# 8-Bluetooth.net
KiCad netlist of a schematic drawn in Altium Designer
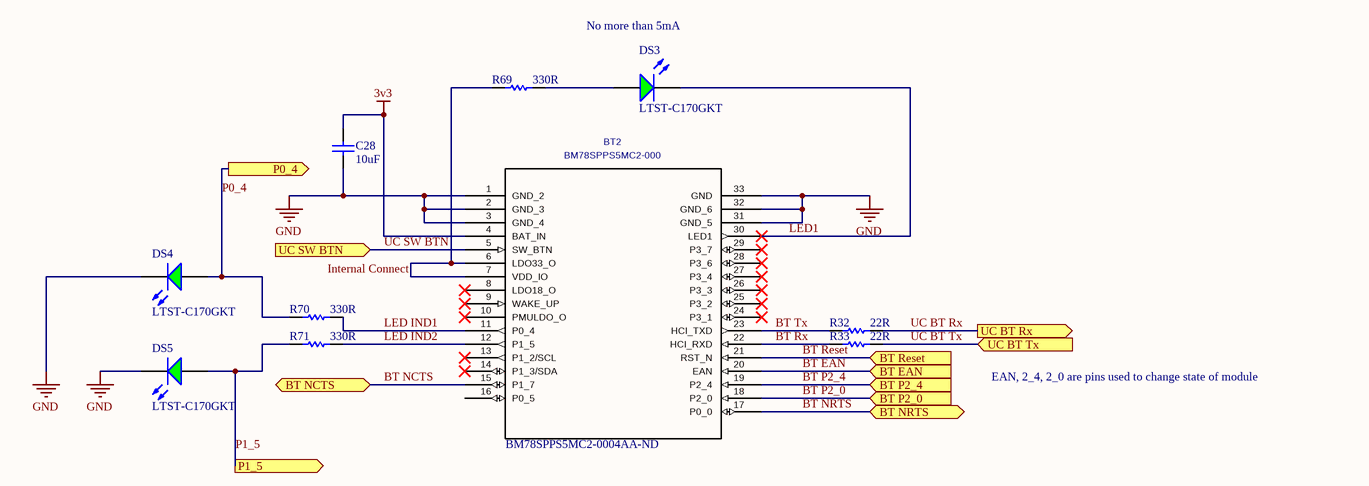
[diagram p0: 8-Bluetooth.SchDoc]

(export (version "E")
  (design (tool "Eeschema 10.0.6"))
  (components
    (comp (ref "BT2")
      (value "BM78SPPS5MC2-000")
      (footprint "BM78SPPS5MC2/NC2")
      (fields
        (field (name "MANUFACTURER_PART_NUMBER") "BM78SPPS5MC2-0006AA")
        (field (name "SUPPLIER PART NUMBER 1") "BM78SPPS5MC2-0004AA-ND")
        (field (name "COPYRIGHT") "Copyright (C) 2022 Ultra Librarian. All rights reserved.")
      )
      (libsource (lib "VCB20") (part "BM78SPPS5MC2-000"))
    )
    (comp (ref "C28")
      (value "10uF")
      (footprint "1608[0603]")
      (description "Capacitor")
      (fields
        (field (name "MANUFACTURER") "Yageo")
        (field (name "MANUFACTURER PART NUMBER") "CC0603KRX7R9BB104")
      )
      (libsource (lib "Miscellaneous Devices") (part "Cap"))
    )
    (comp (ref "DS3")
      (value "LTST-C170GKT")
      (footprint "LTST-C170GKT_V")
      (description "LED Uni-Color Green, 100 mW, 120 mA, -55 to 85 degC, 2-Pin SMD, RoHS, Tape and Reel")
      (fields (field (name "MANUFACTURER") "Lite-On"))
      (libsource (lib "Altium Content Vault") (part "LED-GREEN-AK-2"))
    )
    (comp (ref "DS4")
      (value "LTST-C170GKT")
      (footprint "LTST-C170GKT_V")
      (description "LED Uni-Color Green, 100 mW, 120 mA, -55 to 85 degC, 2-Pin SMD, RoHS, Tape and Reel")
      (fields (field (name "MANUFACTURER") "Lite-On"))
      (libsource (lib "Altium Content Vault") (part "LED-GREEN-AK-2"))
    )
    (comp (ref "DS5")
      (value "LTST-C170GKT")
      (footprint "LTST-C170GKT_V")
      (description "LED Uni-Color Green, 100 mW, 120 mA, -55 to 85 degC, 2-Pin SMD, RoHS, Tape and Reel")
      (fields (field (name "MANUFACTURER") "Lite-On"))
      (libsource (lib "Altium Content Vault") (part "LED-GREEN-AK-2"))
    )
    (comp (ref "R32")
      (value "22R")
      (footprint "1608[0603]")
      (description "Resistor")
      (fields
        (field (name "MANUFACTURER") "Yageo")
        (field (name "MANUFACTURER PART NUMBER") "RC0603JR-0722RL")
      )
      (libsource (lib "Miscellaneous Devices") (part "Res1"))
    )
    (comp (ref "R33")
      (value "22R")
      (footprint "1608[0603]")
      (description "Resistor")
      (fields
        (field (name "MANUFACTURER") "Yageo")
        (field (name "MANUFACTURER PART NUMBER") "RC0603JR-0722RL")
      )
      (libsource (lib "Miscellaneous Devices") (part "Res1"))
    )
    (comp (ref "R69")
      (value "330R")
      (footprint "1608[0603]")
      (description "Resistor")
      (fields
        (field (name "MANUFACTURER") "Yageo")
        (field (name "MANUFACTURER PART NUMBER") "RC0603JR-0722RL")
      )
      (libsource (lib "Miscellaneous Devices") (part "Res1"))
    )
    (comp (ref "R70")
      (value "330R")
      (footprint "1608[0603]")
      (description "Resistor")
      (fields
        (field (name "MANUFACTURER") "Yageo")
        (field (name "MANUFACTURER PART NUMBER") "RC0603JR-0722RL")
      )
      (libsource (lib "Miscellaneous Devices") (part "Res1"))
    )
    (comp (ref "R71")
      (value "330R")
      (footprint "1608[0603]")
      (description "Resistor")
      (fields
        (field (name "MANUFACTURER") "Yageo")
        (field (name "MANUFACTURER PART NUMBER") "RC0603JR-0722RL")
      )
      (libsource (lib "Miscellaneous Devices") (part "Res1"))
    )
  )
  (nets
    (net (code "1") (name "/BT EAN") (class "Default")
      (node (ref "BT2") (pin "20") (pinfunction "EAN_20") (pintype "input"))
    )
    (net (code "2") (name "/BT NCTS") (class "Default")
      (node (ref "BT2") (pin "15") (pinfunction "P1_7_15") (pintype "bidirectional"))
    )
    (net (code "3") (name "/BT NRTS") (class "Default")
      (node (ref "BT2") (pin "17") (pinfunction "P0_0_17") (pintype "bidirectional"))
    )
    (net (code "4") (name "/BT P2_0") (class "Default")
      (node (ref "BT2") (pin "18") (pinfunction "P2_0_18") (pintype "input"))
    )
    (net (code "5") (name "/BT P2_4") (class "Default")
      (node (ref "BT2") (pin "19") (pinfunction "P2_4_19") (pintype "input"))
    )
    (net (code "6") (name "/BT Reset") (class "Default")
      (node (ref "BT2") (pin "21") (pinfunction "RST_N_21") (pintype "input"))
    )
    (net (code "7") (name "/BT Rx") (class "Default")
      (node (ref "BT2") (pin "22") (pinfunction "HCI_RXD_22") (pintype "input"))
      (node (ref "R33") (pin "1") (pinfunction "1_1") (pintype "passive"))
    )
    (net (code "8") (name "/BT Tx") (class "Default")
      (node (ref "BT2") (pin "23") (pinfunction "HCI_TXD_23") (pintype "output"))
      (node (ref "R32") (pin "1") (pinfunction "1_1") (pintype "passive"))
    )
    (net (code "9") (name "/Internal Connect") (class "Default")
      (node (ref "BT2") (pin "6") (pinfunction "LDO33_O_6") (pintype "power_in"))
      (node (ref "BT2") (pin "7") (pinfunction "VDD_IO_7") (pintype "power_in"))
      (node (ref "R69") (pin "1") (pinfunction "1_1") (pintype "passive"))
    )
    (net (code "10") (name "/LED IND1") (class "Default")
      (node (ref "BT2") (pin "11") (pinfunction "P0_4_11") (pintype "output"))
      (node (ref "R70") (pin "2") (pinfunction "2_2") (pintype "passive"))
    )
    (net (code "11") (name "/LED IND2") (class "Default")
      (node (ref "BT2") (pin "12") (pinfunction "P1_5_12") (pintype "output"))
      (node (ref "R71") (pin "2") (pinfunction "2_2") (pintype "passive"))
    )
    (net (code "12") (name "/LED1") (class "Default")
      (node (ref "BT2") (pin "30") (pinfunction "LED1_30") (pintype "output"))
      (node (ref "DS3") (pin "2") (pinfunction "K_2") (pintype "passive"))
    )
    (net (code "13") (name "/P0_4") (class "Default")
      (node (ref "DS4") (pin "1") (pinfunction "A_1") (pintype "passive"))
      (node (ref "R70") (pin "1") (pinfunction "1_1") (pintype "passive"))
    )
    (net (code "14") (name "/P1_5") (class "Default")
      (node (ref "DS5") (pin "1") (pinfunction "A_1") (pintype "passive"))
      (node (ref "R71") (pin "1") (pinfunction "1_1") (pintype "passive"))
    )
    (net (code "15") (name "/UC BT Rx") (class "Default")
      (node (ref "R32") (pin "2") (pinfunction "2_2") (pintype "passive"))
    )
    (net (code "16") (name "/UC BT Tx") (class "Default")
      (node (ref "R33") (pin "2") (pinfunction "2_2") (pintype "passive"))
    )
    (net (code "17") (name "/UC SW BTN") (class "Default")
      (node (ref "BT2") (pin "5") (pinfunction "SW_BTN_5") (pintype "input"))
    )
    (net (code "18") (name "3v3") (class "Default")
      (node (ref "BT2") (pin "4") (pinfunction "BAT_IN_4") (pintype "power_in"))
      (node (ref "C28") (pin "2") (pinfunction "2_2") (pintype "passive"))
    )
    (net (code "19") (name "GND") (class "Default")
      (node (ref "BT2") (pin "1") (pinfunction "GND_2_1") (pintype "power_in"))
      (node (ref "BT2") (pin "2") (pinfunction "GND_3_2") (pintype "power_in"))
      (node (ref "BT2") (pin "3") (pinfunction "GND_4_3") (pintype "power_in"))
      (node (ref "BT2") (pin "31") (pinfunction "GND_5_31") (pintype "power_in"))
      (node (ref "BT2") (pin "32") (pinfunction "GND_6_32") (pintype "power_in"))
      (node (ref "BT2") (pin "33") (pinfunction "GND_33") (pintype "power_in"))
      (node (ref "C28") (pin "1") (pinfunction "1_1") (pintype "passive"))
      (node (ref "DS4") (pin "2") (pinfunction "K_2") (pintype "passive"))
      (node (ref "DS5") (pin "2") (pinfunction "K_2") (pintype "passive"))
    )
    (net (code "20") (name "Net-(DS3-A)") (class "Default")
      (node (ref "DS3") (pin "1") (pinfunction "A_1") (pintype "passive"))
      (node (ref "R69") (pin "2") (pinfunction "2_2") (pintype "passive"))
    )
    (net (code "21") (name "unconnected-(BT2-LDO18_O-Pad8)") (class "Default")
      (node (ref "BT2") (pin "8") (pinfunction "LDO18_O_8") (pintype "power_in+no_connect"))
    )
    (net (code "22") (name "unconnected-(BT2-P0_5-Pad16)") (class "Default")
      (node (ref "BT2") (pin "16") (pinfunction "P0_5_16") (pintype "bidirectional"))
    )
    (net (code "23") (name "unconnected-(BT2-P1_2{slash}SCL-Pad13)") (class "Default")
      (node (ref "BT2") (pin "13") (pinfunction "P1_2/SCL_13") (pintype "output+no_connect"))
    )
    (net (code "24") (name "unconnected-(BT2-P1_3{slash}SDA-Pad14)") (class "Default")
      (node (ref "BT2") (pin "14") (pinfunction "P1_3/SDA_14") (pintype "bidirectional+no_connect"))
    )
    (net (code "25") (name "unconnected-(BT2-P3_1-Pad24)") (class "Default")
      (node (ref "BT2") (pin "24") (pinfunction "P3_1_24") (pintype "bidirectional+no_connect"))
    )
    (net (code "26") (name "unconnected-(BT2-P3_2-Pad25)") (class "Default")
      (node (ref "BT2") (pin "25") (pinfunction "P3_2_25") (pintype "bidirectional+no_connect"))
    )
    (net (code "27") (name "unconnected-(BT2-P3_3-Pad26)") (class "Default")
      (node (ref "BT2") (pin "26") (pinfunction "P3_3_26") (pintype "bidirectional+no_connect"))
    )
    (net (code "28") (name "unconnected-(BT2-P3_4-Pad27)") (class "Default")
      (node (ref "BT2") (pin "27") (pinfunction "P3_4_27") (pintype "bidirectional+no_connect"))
    )
    (net (code "29") (name "unconnected-(BT2-P3_6-Pad28)") (class "Default")
      (node (ref "BT2") (pin "28") (pinfunction "P3_6_28") (pintype "bidirectional+no_connect"))
    )
    (net (code "30") (name "unconnected-(BT2-P3_7-Pad29)") (class "Default")
      (node (ref "BT2") (pin "29") (pinfunction "P3_7_29") (pintype "bidirectional+no_connect"))
    )
    (net (code "31") (name "unconnected-(BT2-PMULDO_O-Pad10)") (class "Default")
      (node (ref "BT2") (pin "10") (pinfunction "PMULDO_O_10") (pintype "power_in+no_connect"))
    )
    (net (code "32") (name "unconnected-(BT2-WAKE_UP-Pad9)") (class "Default")
      (node (ref "BT2") (pin "9") (pinfunction "WAKE_UP_9") (pintype "input+no_connect"))
    )
  )
)
